# JS7628_base_microSD_v1_0.net
KiCad netlist of a schematic drawn in Altium Designer
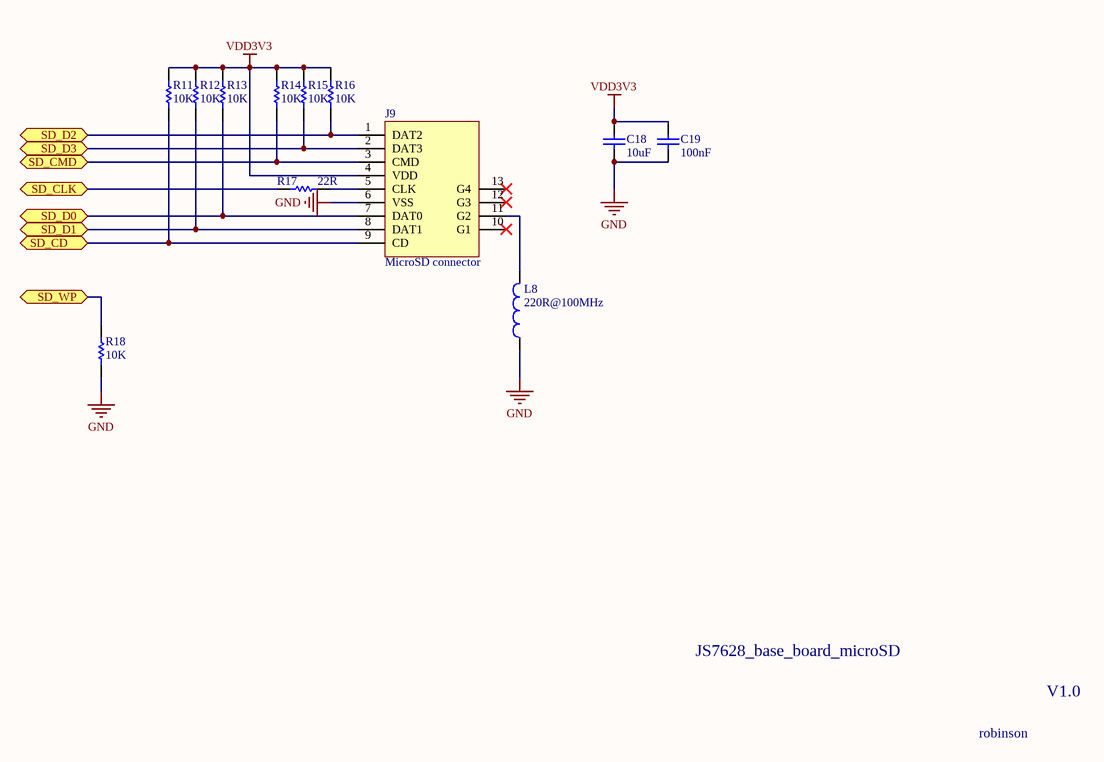
[diagram p0: JS7628_base_microSD_v1.0.SchDoc]

(export (version "E")
  (design (tool "Eeschema 10.0.6"))
  (components
    (comp (ref "C18")
      (value "10uF")
      (footprint "0603")
      (fields (field (name "Comment") "CAP-SMT"))
      (libsource (lib "MyMiscellaneousDevice") (part "CAP-SMT"))
    )
    (comp (ref "C19")
      (value "100nF")
      (footprint "0603")
      (fields (field (name "Comment") "CAP-SMT"))
      (libsource (lib "MyMiscellaneousDevice") (part "CAP-SMT"))
    )
    (comp (ref "J9")
      (value "MicroSD connector")
      (footprint "MyMiscellaneousConnector:MicroSD_connecter")
      (libsource (lib "MyMiscellaneousConnector") (part "MicroSD connector"))
    )
    (comp (ref "L8")
      (value "220R@100MHz")
      (footprint "0603")
      (fields (field (name "Comment") "inductor"))
      (libsource (lib "MyMiscellaneousDevice") (part "inductor"))
    )
    (comp (ref "R11")
      (value "10K")
      (footprint "0603")
      (fields (field (name "Comment") "RES-SMT"))
      (libsource (lib "MyMiscellaneousDevice") (part "RES-SMT"))
    )
    (comp (ref "R12")
      (value "10K")
      (footprint "0603")
      (fields (field (name "Comment") "RES-SMT"))
      (libsource (lib "MyMiscellaneousDevice") (part "RES-SMT"))
    )
    (comp (ref "R13")
      (value "10K")
      (footprint "0603")
      (fields (field (name "Comment") "RES-SMT"))
      (libsource (lib "MyMiscellaneousDevice") (part "RES-SMT"))
    )
    (comp (ref "R14")
      (value "10K")
      (footprint "0603")
      (fields (field (name "Comment") "RES-SMT"))
      (libsource (lib "MyMiscellaneousDevice") (part "RES-SMT"))
    )
    (comp (ref "R15")
      (value "10K")
      (footprint "0603")
      (fields (field (name "Comment") "RES-SMT"))
      (libsource (lib "MyMiscellaneousDevice") (part "RES-SMT"))
    )
    (comp (ref "R16")
      (value "10K")
      (footprint "0603")
      (fields (field (name "Comment") "RES-SMT"))
      (libsource (lib "MyMiscellaneousDevice") (part "RES-SMT"))
    )
    (comp (ref "R17")
      (value "22R")
      (footprint "0603")
      (fields (field (name "Comment") "RES-SMT"))
      (libsource (lib "MyMiscellaneousDevice") (part "RES-SMT"))
    )
    (comp (ref "R18")
      (value "10K")
      (footprint "0603")
      (fields (field (name "Comment") "RES-SMT"))
      (libsource (lib "MyMiscellaneousDevice") (part "RES-SMT"))
    )
  )
  (nets
    (net (code "1") (name "/SD_CD") (class "Default")
      (node (ref "J9") (pin "9") (pinfunction "CD_9") (pintype "passive"))
      (node (ref "R11") (pin "1") (pinfunction "1_1") (pintype "passive"))
    )
    (net (code "2") (name "/SD_CLK") (class "Default")
      (node (ref "R17") (pin "2") (pinfunction "2_2") (pintype "passive"))
    )
    (net (code "3") (name "/SD_CMD") (class "Default")
      (node (ref "J9") (pin "3") (pinfunction "CMD_3") (pintype "passive"))
      (node (ref "R14") (pin "1") (pinfunction "1_1") (pintype "passive"))
    )
    (net (code "4") (name "/SD_D0") (class "Default")
      (node (ref "J9") (pin "7") (pinfunction "DAT0_7") (pintype "passive"))
      (node (ref "R13") (pin "1") (pinfunction "1_1") (pintype "passive"))
    )
    (net (code "5") (name "/SD_D1") (class "Default")
      (node (ref "J9") (pin "8") (pinfunction "DAT1_8") (pintype "passive"))
      (node (ref "R12") (pin "1") (pinfunction "1_1") (pintype "passive"))
    )
    (net (code "6") (name "/SD_D2") (class "Default")
      (node (ref "J9") (pin "1") (pinfunction "DAT2_1") (pintype "passive"))
      (node (ref "R16") (pin "1") (pinfunction "1_1") (pintype "passive"))
    )
    (net (code "7") (name "/SD_D3") (class "Default")
      (node (ref "J9") (pin "2") (pinfunction "DAT3_2") (pintype "passive"))
      (node (ref "R15") (pin "1") (pinfunction "1_1") (pintype "passive"))
    )
    (net (code "8") (name "/SD_WP") (class "Default")
      (node (ref "R18") (pin "2") (pinfunction "2_2") (pintype "passive"))
    )
    (net (code "9") (name "GND") (class "Default")
      (node (ref "C18") (pin "1") (pinfunction "1_1") (pintype "passive"))
      (node (ref "C19") (pin "1") (pinfunction "1_1") (pintype "passive"))
      (node (ref "J9") (pin "6") (pinfunction "VSS_6") (pintype "passive"))
      (node (ref "L8") (pin "1") (pinfunction "1_1") (pintype "passive"))
      (node (ref "R18") (pin "1") (pinfunction "1_1") (pintype "passive"))
    )
    (net (code "10") (name "Net-(J9-CLK)") (class "Default")
      (node (ref "J9") (pin "5") (pinfunction "CLK_5") (pintype "passive"))
      (node (ref "R17") (pin "1") (pinfunction "1_1") (pintype "passive"))
    )
    (net (code "11") (name "Net-(J9-G2)") (class "Default")
      (node (ref "J9") (pin "11") (pinfunction "G2_11") (pintype "passive"))
      (node (ref "L8") (pin "2") (pinfunction "2_2") (pintype "passive"))
    )
    (net (code "12") (name "VDD3V3") (class "Default")
      (node (ref "C18") (pin "2") (pinfunction "2_2") (pintype "passive"))
      (node (ref "C19") (pin "2") (pinfunction "2_2") (pintype "passive"))
      (node (ref "J9") (pin "4") (pinfunction "VDD_4") (pintype "passive"))
      (node (ref "R11") (pin "2") (pinfunction "2_2") (pintype "passive"))
      (node (ref "R12") (pin "2") (pinfunction "2_2") (pintype "passive"))
      (node (ref "R13") (pin "2") (pinfunction "2_2") (pintype "passive"))
      (node (ref "R14") (pin "2") (pinfunction "2_2") (pintype "passive"))
      (node (ref "R15") (pin "2") (pinfunction "2_2") (pintype "passive"))
      (node (ref "R16") (pin "2") (pinfunction "2_2") (pintype "passive"))
    )
    (net (code "13") (name "unconnected-(J9-G1-Pad10)") (class "Default")
      (node (ref "J9") (pin "10") (pinfunction "G1_10") (pintype "passive+no_connect"))
    )
    (net (code "14") (name "unconnected-(J9-G3-Pad12)") (class "Default")
      (node (ref "J9") (pin "12") (pinfunction "G3_12") (pintype "passive+no_connect"))
    )
    (net (code "15") (name "unconnected-(J9-G4-Pad13)") (class "Default")
      (node (ref "J9") (pin "13") (pinfunction "G4_13") (pintype "passive+no_connect"))
    )
  )
)
